# RCM-CamLight_v1.net
KiCad netlist of a schematic drawn in EAGLE
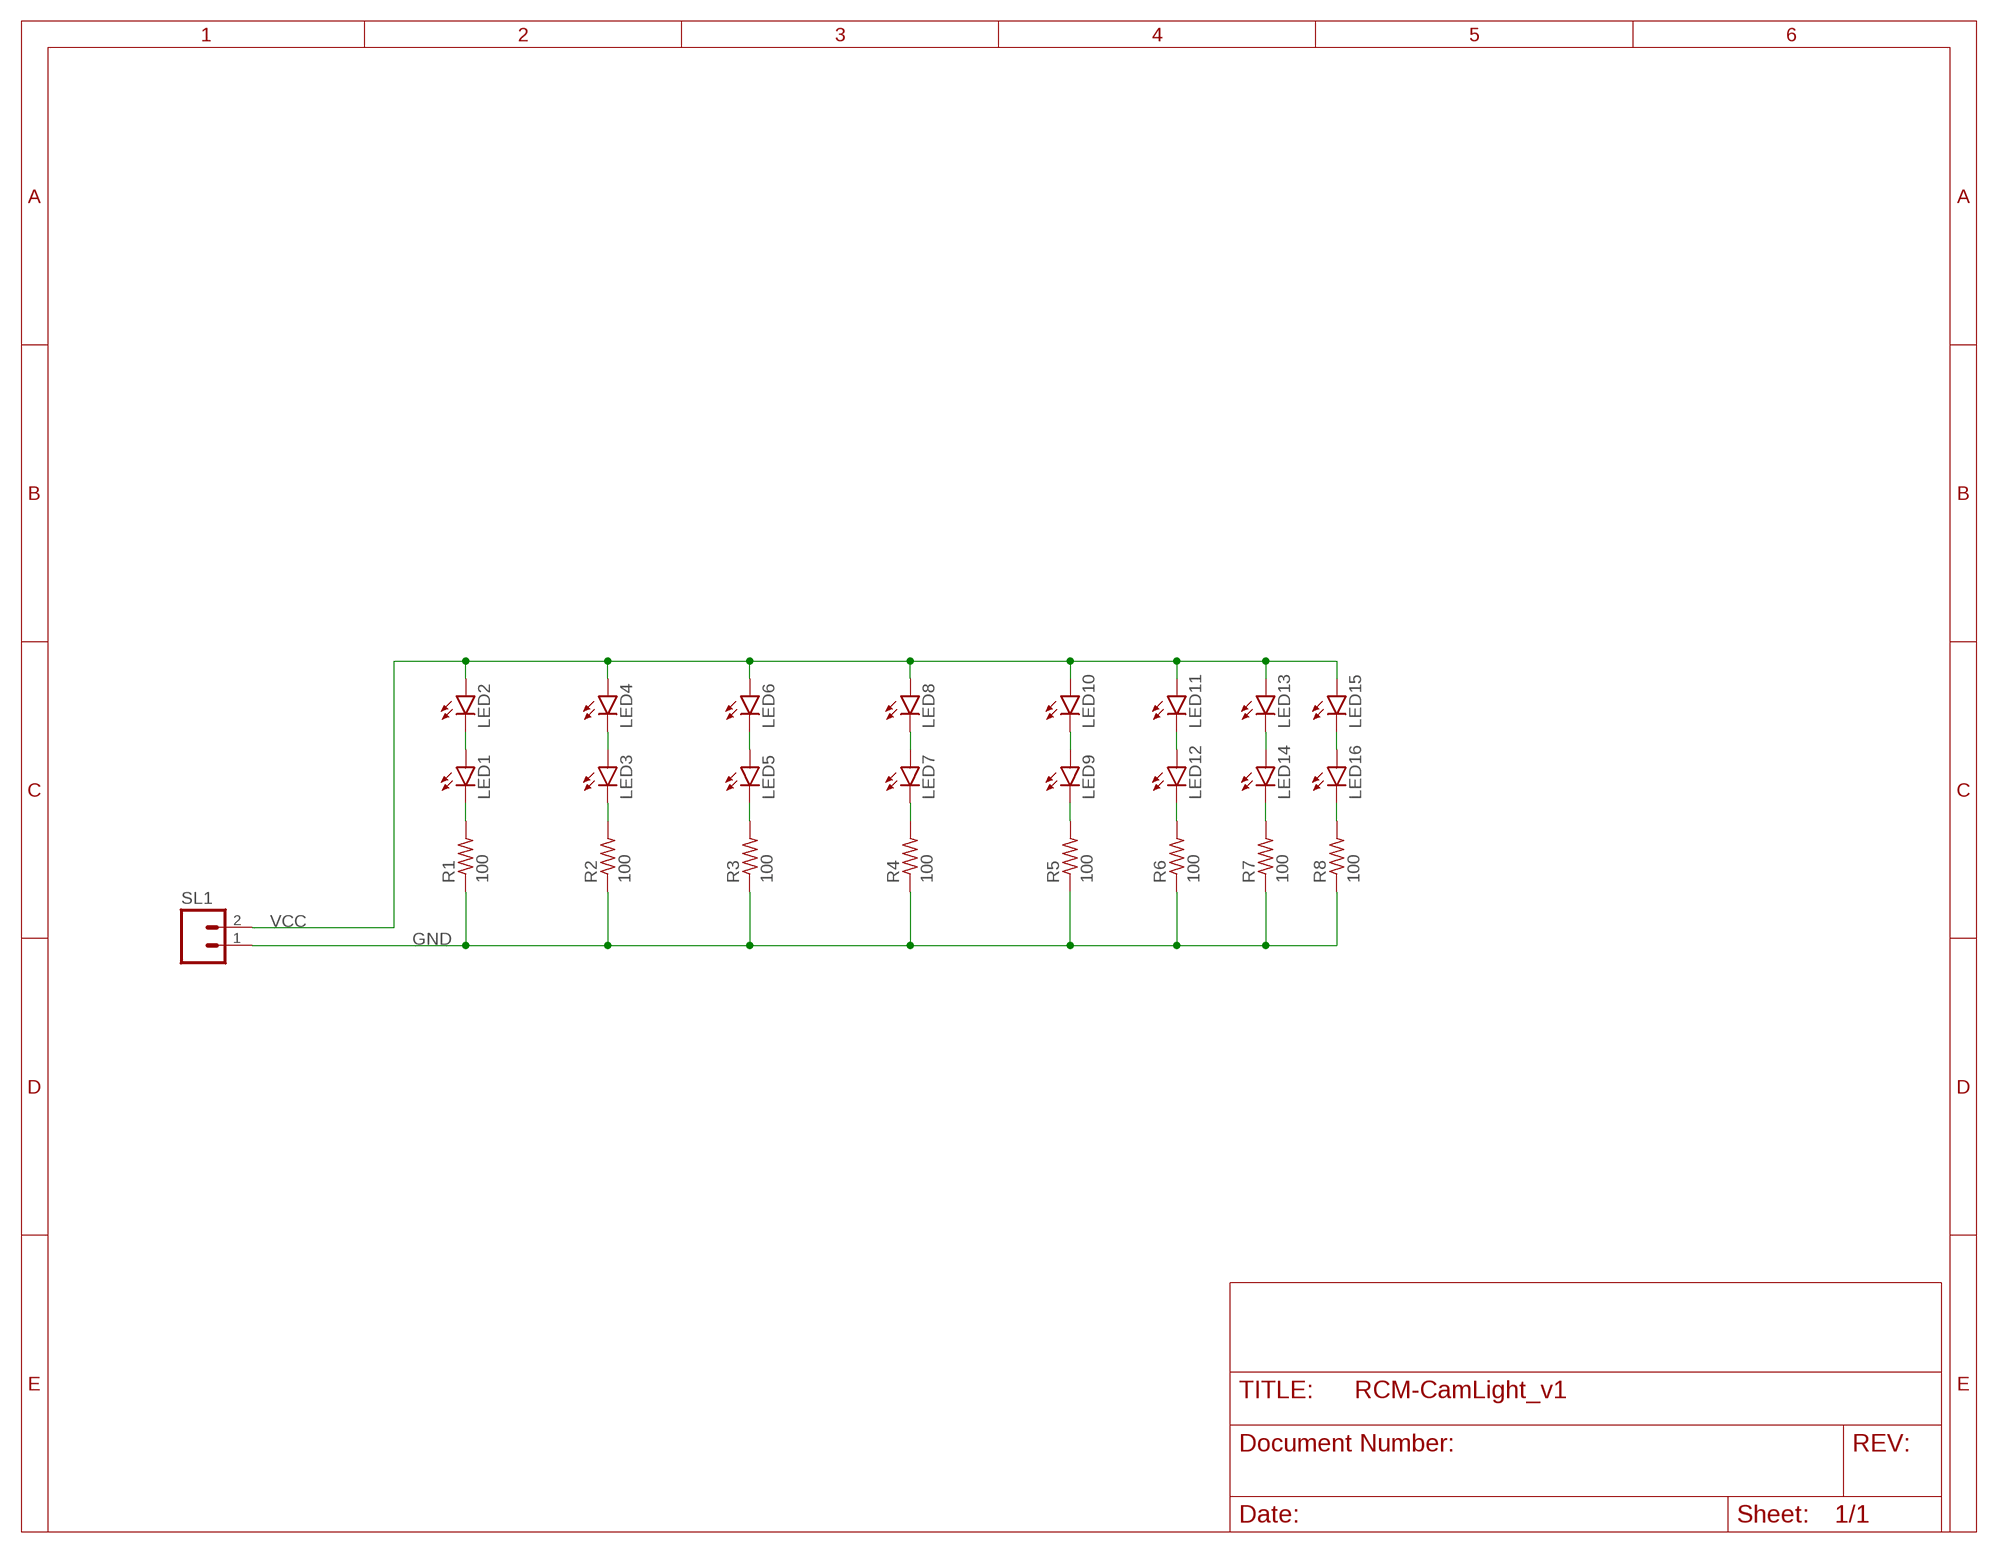
[diagram p0: schematic, sheet 1]

(export (version "E")
  (design (tool "Eeschema 10.0.6"))
  (components
    (comp (ref "LED1")
      (value "LED3MM")
      (footprint "eagle-import:LED3MM")
      (libsource (lib "eagle-import") (part "LED3MM"))
    )
    (comp (ref "LED2")
      (value "LED3MM")
      (footprint "eagle-import:LED3MM")
      (libsource (lib "eagle-import") (part "LED3MM"))
    )
    (comp (ref "LED3")
      (value "LED3MM")
      (footprint "eagle-import:LED3MM")
      (libsource (lib "eagle-import") (part "LED3MM"))
    )
    (comp (ref "LED4")
      (value "LED3MM")
      (footprint "eagle-import:LED3MM")
      (libsource (lib "eagle-import") (part "LED3MM"))
    )
    (comp (ref "LED5")
      (value "LED3MM")
      (footprint "eagle-import:LED3MM")
      (libsource (lib "eagle-import") (part "LED3MM"))
    )
    (comp (ref "LED6")
      (value "LED3MM")
      (footprint "eagle-import:LED3MM")
      (libsource (lib "eagle-import") (part "LED3MM"))
    )
    (comp (ref "LED7")
      (value "LED3MM")
      (footprint "eagle-import:LED3MM")
      (libsource (lib "eagle-import") (part "LED3MM"))
    )
    (comp (ref "LED8")
      (value "LED3MM")
      (footprint "eagle-import:LED3MM")
      (libsource (lib "eagle-import") (part "LED3MM"))
    )
    (comp (ref "LED9")
      (value "LED3MM")
      (footprint "eagle-import:LED3MM")
      (libsource (lib "eagle-import") (part "LED3MM"))
    )
    (comp (ref "LED10")
      (value "LED3MM")
      (footprint "eagle-import:LED3MM")
      (libsource (lib "eagle-import") (part "LED3MM"))
    )
    (comp (ref "LED11")
      (value "LED3MM")
      (footprint "eagle-import:LED3MM")
      (libsource (lib "eagle-import") (part "LED3MM"))
    )
    (comp (ref "LED12")
      (value "LED3MM")
      (footprint "eagle-import:LED3MM")
      (libsource (lib "eagle-import") (part "LED3MM"))
    )
    (comp (ref "LED13")
      (value "LED3MM")
      (footprint "eagle-import:LED3MM")
      (libsource (lib "eagle-import") (part "LED3MM"))
    )
    (comp (ref "LED14")
      (value "LED3MM")
      (footprint "eagle-import:LED3MM")
      (libsource (lib "eagle-import") (part "LED3MM"))
    )
    (comp (ref "LED15")
      (value "LED3MM")
      (footprint "eagle-import:LED3MM")
      (libsource (lib "eagle-import") (part "LED3MM"))
    )
    (comp (ref "LED16")
      (value "LED3MM")
      (footprint "eagle-import:LED3MM")
      (libsource (lib "eagle-import") (part "LED3MM"))
    )
    (comp (ref "R1")
      (value "100")
      (footprint "eagle-import:0204_7")
      (libsource (lib "eagle-import") (part "R-US_0204/7"))
    )
    (comp (ref "R2")
      (value "100")
      (footprint "eagle-import:0204_7")
      (libsource (lib "eagle-import") (part "R-US_0204/7"))
    )
    (comp (ref "R3")
      (value "100")
      (footprint "eagle-import:0204_7")
      (libsource (lib "eagle-import") (part "R-US_0204/7"))
    )
    (comp (ref "R4")
      (value "100")
      (footprint "eagle-import:0204_7")
      (libsource (lib "eagle-import") (part "R-US_0204/7"))
    )
    (comp (ref "R5")
      (value "100")
      (footprint "eagle-import:0204_7")
      (libsource (lib "eagle-import") (part "R-US_0204/7"))
    )
    (comp (ref "R6")
      (value "100")
      (footprint "eagle-import:0204_7")
      (libsource (lib "eagle-import") (part "R-US_0204/7"))
    )
    (comp (ref "R7")
      (value "100")
      (footprint "eagle-import:0204_7")
      (libsource (lib "eagle-import") (part "R-US_0204/7"))
    )
    (comp (ref "R8")
      (value "100")
      (footprint "eagle-import:0204_7")
      (libsource (lib "eagle-import") (part "R-US_0204/7"))
    )
    (comp (ref "SL1")
      (value "M02")
      (footprint "eagle-import:02P")
      (libsource (lib "eagle-import") (part "M02"))
    )
  )
  (nets
    (net (code "1") (name "/GND") (class "Default")
      (node (ref "R1") (pin "1") (pinfunction "1_1") (pintype "passive"))
      (node (ref "R2") (pin "1") (pinfunction "1_1") (pintype "passive"))
      (node (ref "R3") (pin "1") (pinfunction "1_1") (pintype "passive"))
      (node (ref "R4") (pin "1") (pinfunction "1_1") (pintype "passive"))
      (node (ref "R5") (pin "1") (pinfunction "1_1") (pintype "passive"))
      (node (ref "R6") (pin "1") (pinfunction "1_1") (pintype "passive"))
      (node (ref "R7") (pin "1") (pinfunction "1_1") (pintype "passive"))
      (node (ref "R8") (pin "1") (pinfunction "1_1") (pintype "passive"))
      (node (ref "SL1") (pin "1") (pinfunction "1_1") (pintype "passive"))
    )
    (net (code "2") (name "/VCC") (class "Default")
      (node (ref "LED10") (pin "A") (pinfunction "A_A") (pintype "passive"))
      (node (ref "LED11") (pin "A") (pinfunction "A_A") (pintype "passive"))
      (node (ref "LED13") (pin "A") (pinfunction "A_A") (pintype "passive"))
      (node (ref "LED15") (pin "A") (pinfunction "A_A") (pintype "passive"))
      (node (ref "LED2") (pin "A") (pinfunction "A_A") (pintype "passive"))
      (node (ref "LED4") (pin "A") (pinfunction "A_A") (pintype "passive"))
      (node (ref "LED6") (pin "A") (pinfunction "A_A") (pintype "passive"))
      (node (ref "LED8") (pin "A") (pinfunction "A_A") (pintype "passive"))
      (node (ref "SL1") (pin "2") (pinfunction "2_2") (pintype "passive"))
    )
    (net (code "3") (name "Net-(LED1-C)") (class "Default")
      (node (ref "LED1") (pin "K") (pinfunction "C_K") (pintype "passive"))
      (node (ref "R1") (pin "2") (pinfunction "2_2") (pintype "passive"))
    )
    (net (code "4") (name "Net-(LED2-C)") (class "Default")
      (node (ref "LED1") (pin "A") (pinfunction "A_A") (pintype "passive"))
      (node (ref "LED2") (pin "K") (pinfunction "C_K") (pintype "passive"))
    )
    (net (code "5") (name "Net-(LED3-C)") (class "Default")
      (node (ref "LED3") (pin "K") (pinfunction "C_K") (pintype "passive"))
      (node (ref "R2") (pin "2") (pinfunction "2_2") (pintype "passive"))
    )
    (net (code "6") (name "Net-(LED4-C)") (class "Default")
      (node (ref "LED3") (pin "A") (pinfunction "A_A") (pintype "passive"))
      (node (ref "LED4") (pin "K") (pinfunction "C_K") (pintype "passive"))
    )
    (net (code "7") (name "Net-(LED5-C)") (class "Default")
      (node (ref "LED5") (pin "K") (pinfunction "C_K") (pintype "passive"))
      (node (ref "R3") (pin "2") (pinfunction "2_2") (pintype "passive"))
    )
    (net (code "8") (name "Net-(LED6-C)") (class "Default")
      (node (ref "LED5") (pin "A") (pinfunction "A_A") (pintype "passive"))
      (node (ref "LED6") (pin "K") (pinfunction "C_K") (pintype "passive"))
    )
    (net (code "9") (name "Net-(LED7-C)") (class "Default")
      (node (ref "LED7") (pin "K") (pinfunction "C_K") (pintype "passive"))
      (node (ref "R4") (pin "2") (pinfunction "2_2") (pintype "passive"))
    )
    (net (code "10") (name "Net-(LED8-C)") (class "Default")
      (node (ref "LED7") (pin "A") (pinfunction "A_A") (pintype "passive"))
      (node (ref "LED8") (pin "K") (pinfunction "C_K") (pintype "passive"))
    )
    (net (code "11") (name "Net-(LED9-C)") (class "Default")
      (node (ref "LED9") (pin "K") (pinfunction "C_K") (pintype "passive"))
      (node (ref "R5") (pin "2") (pinfunction "2_2") (pintype "passive"))
    )
    (net (code "12") (name "Net-(LED10-C)") (class "Default")
      (node (ref "LED10") (pin "K") (pinfunction "C_K") (pintype "passive"))
      (node (ref "LED9") (pin "A") (pinfunction "A_A") (pintype "passive"))
    )
    (net (code "13") (name "Net-(LED11-C)") (class "Default")
      (node (ref "LED11") (pin "K") (pinfunction "C_K") (pintype "passive"))
      (node (ref "LED12") (pin "A") (pinfunction "A_A") (pintype "passive"))
    )
    (net (code "14") (name "Net-(LED12-C)") (class "Default")
      (node (ref "LED12") (pin "K") (pinfunction "C_K") (pintype "passive"))
      (node (ref "R6") (pin "2") (pinfunction "2_2") (pintype "passive"))
    )
    (net (code "15") (name "Net-(LED13-C)") (class "Default")
      (node (ref "LED13") (pin "K") (pinfunction "C_K") (pintype "passive"))
      (node (ref "LED14") (pin "A") (pinfunction "A_A") (pintype "passive"))
    )
    (net (code "16") (name "Net-(LED14-C)") (class "Default")
      (node (ref "LED14") (pin "K") (pinfunction "C_K") (pintype "passive"))
      (node (ref "R7") (pin "2") (pinfunction "2_2") (pintype "passive"))
    )
    (net (code "17") (name "Net-(LED15-C)") (class "Default")
      (node (ref "LED15") (pin "K") (pinfunction "C_K") (pintype "passive"))
      (node (ref "LED16") (pin "A") (pinfunction "A_A") (pintype "passive"))
    )
    (net (code "18") (name "Net-(LED16-C)") (class "Default")
      (node (ref "LED16") (pin "K") (pinfunction "C_K") (pintype "passive"))
      (node (ref "R8") (pin "2") (pinfunction "2_2") (pintype "passive"))
    )
  )
)
